# Simplified_4_ch_sample-and-hold_without_.net
KiCad netlist of a schematic drawn in EAGLE
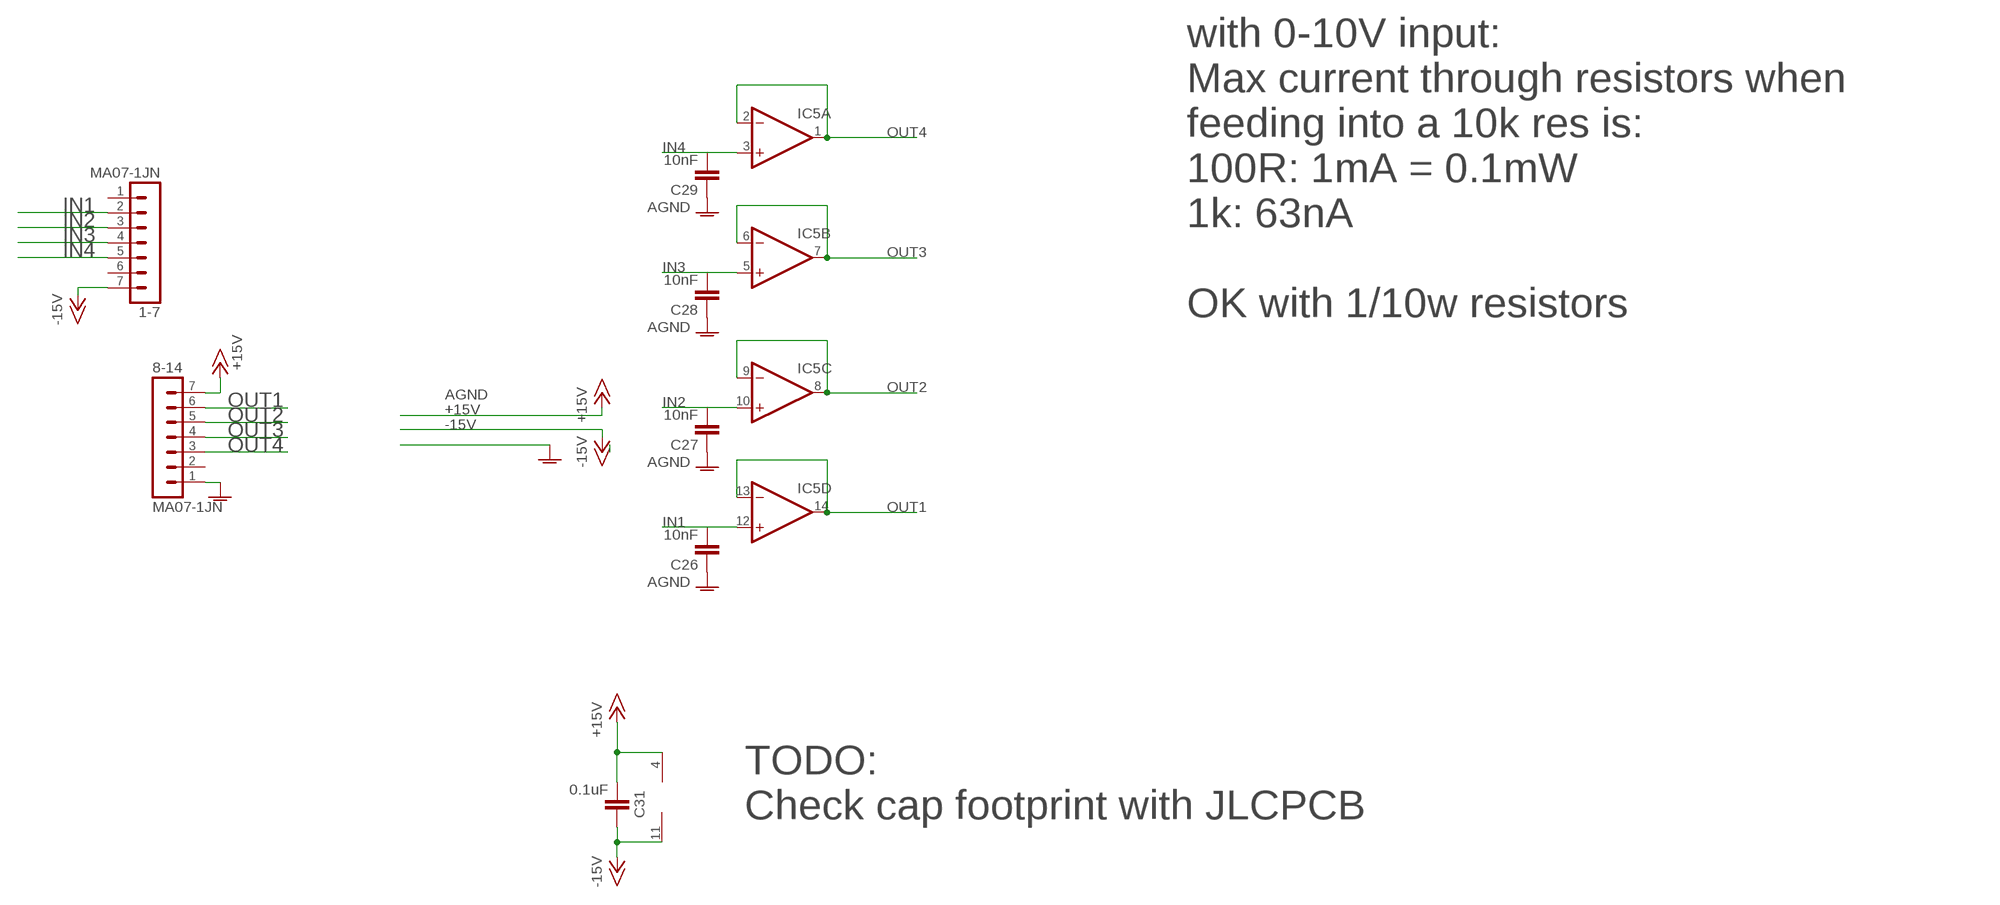
[diagram p0: schematic, sheet 1]

(export (version "E")
  (design (tool "Eeschema 10.0.6"))
  (components
    (comp (ref "1-7")
      (value "MA07-1JN")
      (footprint "eagle-import:MA07N-1J")
      (libsource (lib "eagle-import") (part "MA07-1JN"))
    )
    (comp (ref "8-14")
      (value "MA07-1JN")
      (footprint "eagle-import:MA07N-1J")
      (libsource (lib "eagle-import") (part "MA07-1JN"))
    )
    (comp (ref "C26")
      (value "10nF")
      (footprint "eagle-import:C0805")
      (libsource (lib "eagle-import") (part "C-EUC0805"))
    )
    (comp (ref "C27")
      (value "10nF")
      (footprint "eagle-import:C0805")
      (libsource (lib "eagle-import") (part "C-EUC0805"))
    )
    (comp (ref "C28")
      (value "10nF")
      (footprint "eagle-import:C0805")
      (libsource (lib "eagle-import") (part "C-EUC0805"))
    )
    (comp (ref "C29")
      (value "10nF")
      (footprint "eagle-import:C0805")
      (libsource (lib "eagle-import") (part "C-EUC0805"))
    )
    (comp (ref "C31")
      (value "0.1uF")
      (footprint "eagle-import:C0603")
      (libsource (lib "eagle-import") (part "resistor_C-EUC0603"))
    )
    (comp (ref "IC5")
      (value "TL084CPWR")
      (footprint "eagle-import:TSSOP14J")
      (libsource (lib "eagle-import") (part "TL074JT"))
    )
  )
  (nets
    (net (code "1") (name "+15V") (class "Default")
      (node (ref "8-14") (pin "7") (pinfunction "7_7") (pintype "passive"))
      (node (ref "C31") (pin "1") (pinfunction "1_1") (pintype "passive"))
      (node (ref "IC5") (pin "4") (pinfunction "V+_4") (pintype "power_in"))
    )
    (net (code "2") (name "-15V") (class "Default")
      (node (ref "1-7") (pin "7") (pinfunction "7_7") (pintype "passive"))
      (node (ref "C31") (pin "2") (pinfunction "2_2") (pintype "passive"))
      (node (ref "IC5") (pin "11") (pinfunction "V-_11") (pintype "power_in"))
    )
    (net (code "3") (name "/IN1") (class "Default")
      (node (ref "1-7") (pin "2") (pinfunction "2_2") (pintype "passive"))
      (node (ref "C26") (pin "2") (pinfunction "2_2") (pintype "passive"))
      (node (ref "IC5") (pin "12") (pinfunction "+IN_12") (pintype "input"))
    )
    (net (code "4") (name "/IN2") (class "Default")
      (node (ref "1-7") (pin "3") (pinfunction "3_3") (pintype "passive"))
      (node (ref "C27") (pin "2") (pinfunction "2_2") (pintype "passive"))
      (node (ref "IC5") (pin "10") (pinfunction "+IN_10") (pintype "input"))
    )
    (net (code "5") (name "/IN3") (class "Default")
      (node (ref "1-7") (pin "4") (pinfunction "4_4") (pintype "passive"))
      (node (ref "C28") (pin "2") (pinfunction "2_2") (pintype "passive"))
      (node (ref "IC5") (pin "5") (pinfunction "+IN_5") (pintype "input"))
    )
    (net (code "6") (name "/IN4") (class "Default")
      (node (ref "1-7") (pin "5") (pinfunction "5_5") (pintype "passive"))
      (node (ref "C29") (pin "2") (pinfunction "2_2") (pintype "passive"))
      (node (ref "IC5") (pin "3") (pinfunction "+IN_3") (pintype "input"))
    )
    (net (code "7") (name "/OUT1") (class "Default")
      (node (ref "8-14") (pin "6") (pinfunction "6_6") (pintype "passive"))
      (node (ref "IC5") (pin "13") (pinfunction "-IN_13") (pintype "input"))
      (node (ref "IC5") (pin "14") (pinfunction "OUT_14") (pintype "output"))
    )
    (net (code "8") (name "/OUT2") (class "Default")
      (node (ref "8-14") (pin "5") (pinfunction "5_5") (pintype "passive"))
      (node (ref "IC5") (pin "8") (pinfunction "OUT_8") (pintype "output"))
      (node (ref "IC5") (pin "9") (pinfunction "-IN_9") (pintype "input"))
    )
    (net (code "9") (name "/OUT3") (class "Default")
      (node (ref "8-14") (pin "4") (pinfunction "4_4") (pintype "passive"))
      (node (ref "IC5") (pin "6") (pinfunction "-IN_6") (pintype "input"))
      (node (ref "IC5") (pin "7") (pinfunction "OUT_7") (pintype "output"))
    )
    (net (code "10") (name "/OUT4") (class "Default")
      (node (ref "8-14") (pin "3") (pinfunction "3_3") (pintype "passive"))
      (node (ref "IC5") (pin "1") (pinfunction "OUT_1") (pintype "output"))
      (node (ref "IC5") (pin "2") (pinfunction "-IN_2") (pintype "input"))
    )
    (net (code "11") (name "AGND") (class "Default")
      (node (ref "8-14") (pin "1") (pinfunction "1_1") (pintype "passive"))
      (node (ref "C26") (pin "1") (pinfunction "1_1") (pintype "passive"))
      (node (ref "C27") (pin "1") (pinfunction "1_1") (pintype "passive"))
      (node (ref "C28") (pin "1") (pinfunction "1_1") (pintype "passive"))
      (node (ref "C29") (pin "1") (pinfunction "1_1") (pintype "passive"))
    )
    (net (code "12") (name "unconnected-(1-7-Pad1)") (class "Default")
      (node (ref "1-7") (pin "1") (pinfunction "1_1") (pintype "passive"))
    )
    (net (code "13") (name "unconnected-(1-7-Pad6)") (class "Default")
      (node (ref "1-7") (pin "6") (pinfunction "6_6") (pintype "passive"))
    )
    (net (code "14") (name "unconnected-(8-14-Pad2)") (class "Default")
      (node (ref "8-14") (pin "2") (pinfunction "2_2") (pintype "passive"))
    )
  )
)
